# ISOSPI.net
KiCad netlist of a schematic drawn in Altium Designer
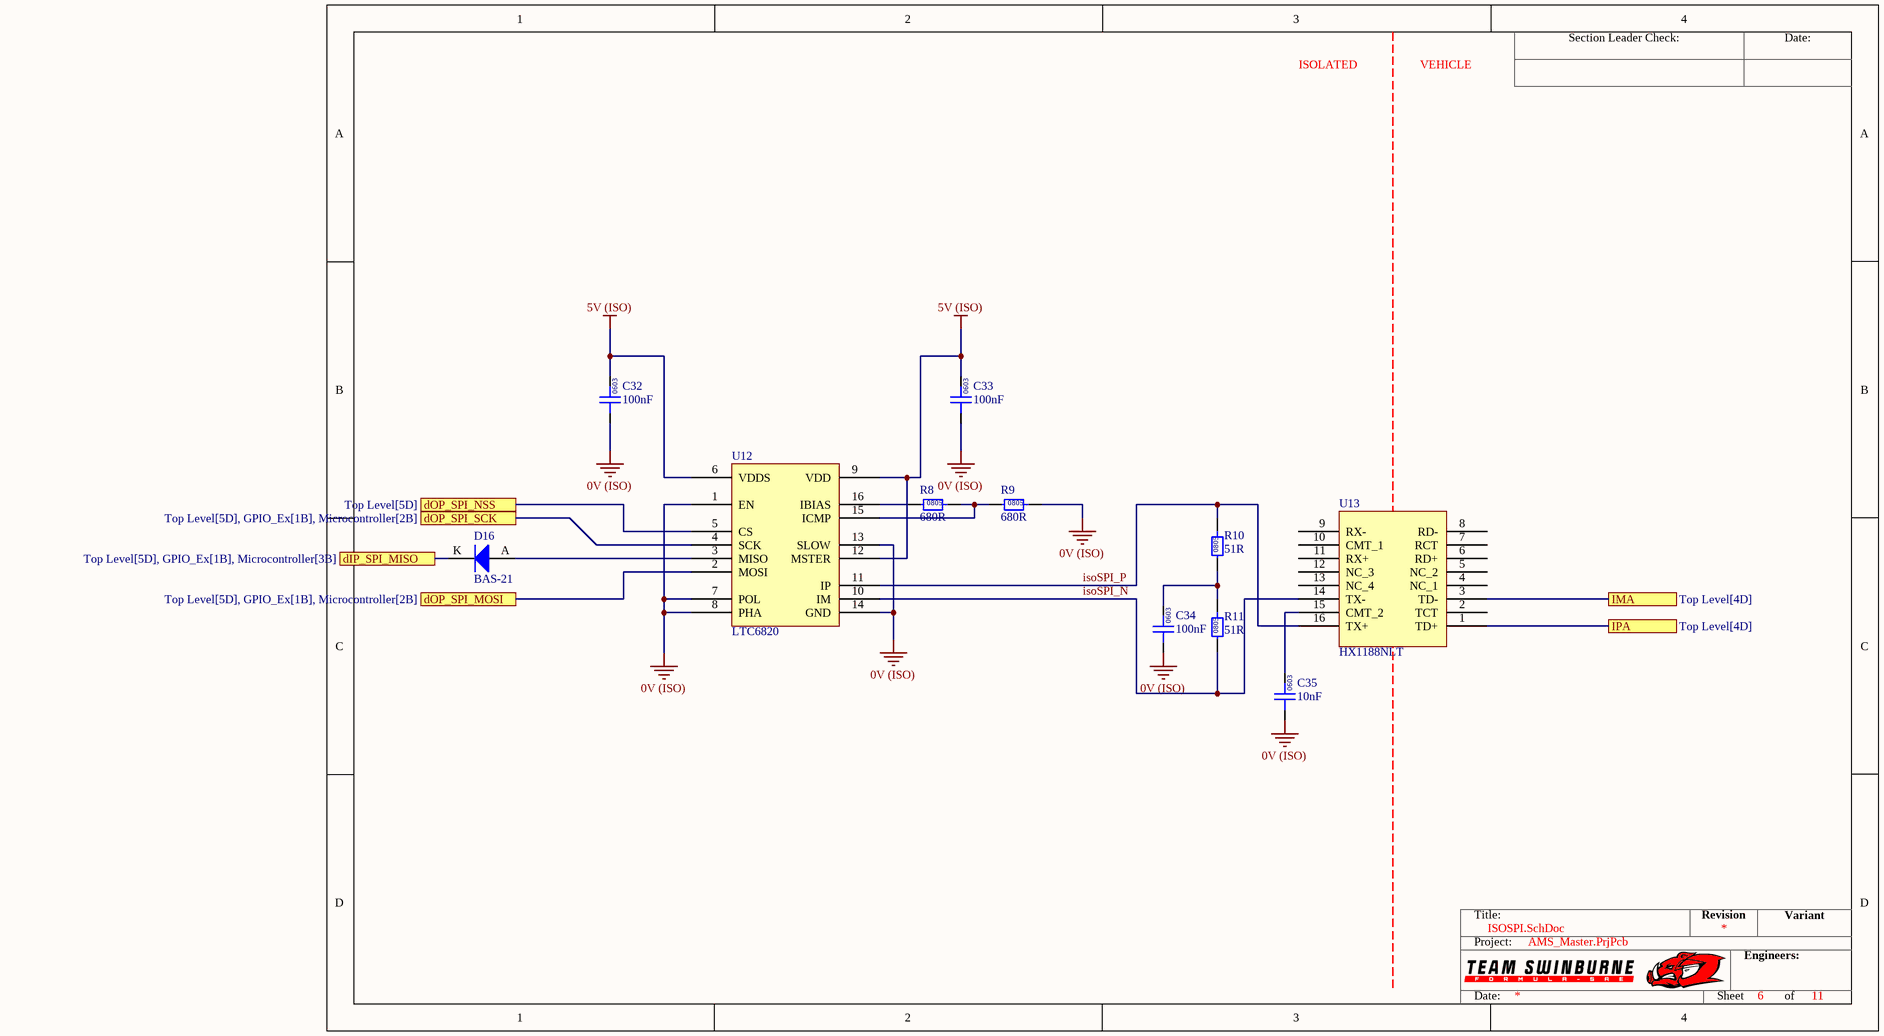
[diagram p0: ISOSPI.SchDoc]

(export (version "E")
  (design (tool "Eeschema 10.0.6"))
  (components
    (comp (ref "C32")
      (value "100nF")
      (footprint "0603")
      (fields
        (field (name "PART NUMBER") "GCM188L81H104KA57D")
        (field (name "MANUFACTURER") "muRata")
        (field (name "TOLERANCE") "±10%")
      )
      (libsource (lib "ts_standard_library") (part "Capacitor 0603"))
    )
    (comp (ref "C33")
      (value "100nF")
      (footprint "0603")
      (fields
        (field (name "PART NUMBER") "GCM188L81H104KA57D")
        (field (name "MANUFACTURER") "muRata")
        (field (name "TOLERANCE") "±10%")
      )
      (libsource (lib "ts_standard_library") (part "Capacitor 0603"))
    )
    (comp (ref "C34")
      (value "100nF")
      (footprint "0603")
      (fields
        (field (name "PART NUMBER") "GCM188L81H104KA57D")
        (field (name "MANUFACTURER") "muRata")
        (field (name "TOLERANCE") "±10%")
      )
      (libsource (lib "ts_standard_library") (part "Capacitor 0603"))
    )
    (comp (ref "C35")
      (value "10nF")
      (footprint "0603")
      (fields
        (field (name "PART NUMBER") "GCM188L81H103KA03D")
        (field (name "MANUFACTURER") "muRata")
        (field (name "TOLERANCE") "±10%")
      )
      (libsource (lib "ts_standard_library") (part "Capacitor 0603"))
    )
    (comp (ref "D16")
      (value "BAS-21")
      (footprint "NEXPERIA_SOT23")
      (fields (field (name "MANUFACTURER") "Nexperia USA Inc."))
      (libsource (lib "ts_standard_library") (part "Diode"))
    )
    (comp (ref "R8")
      (value "680R")
      (footprint "0805")
      (fields
        (field (name "PART NUMBER") "RC0805FR07680RL")
        (field (name "MANUFACTURER") "YAGEO")
        (field (name "TOLERANCE") "0.01")
      )
      (libsource (lib "ts_standard_library") (part "Resistor 0805"))
    )
    (comp (ref "R9")
      (value "680R")
      (footprint "0805")
      (fields
        (field (name "PART NUMBER") "RC0805FR07680RL")
        (field (name "MANUFACTURER") "YAGEO")
        (field (name "TOLERANCE") "0.01")
      )
      (libsource (lib "ts_standard_library") (part "Resistor 0805"))
    )
    (comp (ref "R10")
      (value "51R")
      (footprint "0805")
      (fields
        (field (name "PART NUMBER") "RC0805FR0751RL")
        (field (name "MANUFACTURER") "YAGEO")
        (field (name "TOLERANCE") "0.01")
      )
      (libsource (lib "ts_standard_library") (part "Resistor 0805"))
    )
    (comp (ref "R11")
      (value "51R")
      (footprint "0805")
      (fields
        (field (name "PART NUMBER") "RC0805FR0751RL")
        (field (name "MANUFACTURER") "YAGEO")
        (field (name "TOLERANCE") "0.01")
      )
      (libsource (lib "ts_standard_library") (part "Resistor 0805"))
    )
    (comp (ref "U12")
      (value "LTC6820")
      (footprint "WFQN-16")
      (description "isoSPI Transceiver")
      (fields (field (name "MANUFACTURER") "Analogue Devices"))
      (libsource (lib "ts_standard_library") (part "LTC6820"))
    )
    (comp (ref "U13")
      (value "HX1188NLT")
      (footprint "HX1188NL")
      (description "MODULE XFRMR SGL ETHR LAN 16SOIC")
      (fields (field (name "PART NUMBER") "HX1188NL") (field (name "MANUFACTURER") "Analogue Devices"))
      (libsource (lib "ts_standard_library") (part "HX1188NLT"))
    )
  )
  (nets
    (net (code "1") (name "/IMA") (class "Default")
      (node (ref "U13") (pin "3") (pinfunction "TD-_3") (pintype "passive"))
    )
    (net (code "2") (name "/IPA") (class "Default")
      (node (ref "U13") (pin "1") (pinfunction "TD+_1") (pintype "passive"))
    )
    (net (code "3") (name "/dIP_SPI_MISO") (class "Default")
      (node (ref "D16") (pin "K") (pinfunction "K_K") (pintype "passive"))
    )
    (net (code "4") (name "/dOP_SPI_MOSI") (class "Default")
      (node (ref "U12") (pin "2") (pinfunction "MOSI_2") (pintype "passive"))
    )
    (net (code "5") (name "/dOP_SPI_NSS") (class "Default")
      (node (ref "U12") (pin "5") (pinfunction "CS_5") (pintype "passive"))
    )
    (net (code "6") (name "/dOP_SPI_SCK") (class "Default")
      (node (ref "U12") (pin "4") (pinfunction "SCK_4") (pintype "passive"))
    )
    (net (code "7") (name "/isoSPI_N") (class "Default")
      (node (ref "R11") (pin "1") (pinfunction "1_1") (pintype "passive"))
      (node (ref "U12") (pin "10") (pinfunction "IM_10") (pintype "passive"))
      (node (ref "U13") (pin "14") (pinfunction "TX-_14") (pintype "passive"))
    )
    (net (code "8") (name "/isoSPI_P") (class "Default")
      (node (ref "R10") (pin "2") (pinfunction "2_2") (pintype "passive"))
      (node (ref "U12") (pin "11") (pinfunction "IP_11") (pintype "passive"))
      (node (ref "U13") (pin "16") (pinfunction "TX+_16") (pintype "passive"))
    )
    (net (code "9") (name "0V (ISO)") (class "Default")
      (node (ref "C32") (pin "1") (pinfunction "1_1") (pintype "passive"))
      (node (ref "C33") (pin "1") (pinfunction "1_1") (pintype "passive"))
      (node (ref "C34") (pin "1") (pinfunction "1_1") (pintype "passive"))
      (node (ref "C35") (pin "1") (pinfunction "1_1") (pintype "passive"))
      (node (ref "R9") (pin "2") (pinfunction "2_2") (pintype "passive"))
      (node (ref "U12") (pin "1") (pinfunction "EN_1") (pintype "passive"))
      (node (ref "U12") (pin "13") (pinfunction "SLOW_13") (pintype "passive"))
      (node (ref "U12") (pin "14") (pinfunction "GND_14") (pintype "passive"))
      (node (ref "U12") (pin "7") (pinfunction "POL_7") (pintype "passive"))
      (node (ref "U12") (pin "8") (pinfunction "PHA_8") (pintype "passive"))
    )
    (net (code "10") (name "5V (ISO)") (class "Default")
      (node (ref "C32") (pin "2") (pinfunction "2_2") (pintype "passive"))
      (node (ref "C33") (pin "2") (pinfunction "2_2") (pintype "passive"))
      (node (ref "U12") (pin "12") (pinfunction "MSTER_12") (pintype "passive"))
      (node (ref "U12") (pin "6") (pinfunction "VDDS_6") (pintype "passive"))
      (node (ref "U12") (pin "9") (pinfunction "VDD_9") (pintype "passive"))
    )
    (net (code "11") (name "Net-(C34-Pad2)") (class "Default")
      (node (ref "C34") (pin "2") (pinfunction "2_2") (pintype "passive"))
      (node (ref "R10") (pin "1") (pinfunction "1_1") (pintype "passive"))
      (node (ref "R11") (pin "2") (pinfunction "2_2") (pintype "passive"))
    )
    (net (code "12") (name "Net-(U12-IBIAS)") (class "Default")
      (node (ref "R8") (pin "1") (pinfunction "1_1") (pintype "passive"))
      (node (ref "U12") (pin "16") (pinfunction "IBIAS_16") (pintype "passive"))
    )
    (net (code "13") (name "Net-(U12-ICMP)") (class "Default")
      (node (ref "R8") (pin "2") (pinfunction "2_2") (pintype "passive"))
      (node (ref "R9") (pin "1") (pinfunction "1_1") (pintype "passive"))
      (node (ref "U12") (pin "15") (pinfunction "ICMP_15") (pintype "passive"))
    )
    (net (code "14") (name "Net-(U12-MISO)") (class "Default")
      (node (ref "D16") (pin "A") (pinfunction "A_A") (pintype "passive"))
      (node (ref "U12") (pin "3") (pinfunction "MISO_3") (pintype "passive"))
    )
    (net (code "15") (name "Net-(U13-CMT_2)") (class "Default")
      (node (ref "C35") (pin "2") (pinfunction "2_2") (pintype "passive"))
      (node (ref "U13") (pin "15") (pinfunction "CMT_2_15") (pintype "passive"))
    )
    (net (code "16") (name "unconnected-(U13-CMT_1-Pad10)") (class "Default")
      (node (ref "U13") (pin "10") (pinfunction "CMT_1_10") (pintype "passive"))
    )
    (net (code "17") (name "unconnected-(U13-NC_1-Pad4)") (class "Default")
      (node (ref "U13") (pin "4") (pinfunction "NC_1_4") (pintype "passive"))
    )
    (net (code "18") (name "unconnected-(U13-NC_2-Pad5)") (class "Default")
      (node (ref "U13") (pin "5") (pinfunction "NC_2_5") (pintype "passive"))
    )
    (net (code "19") (name "unconnected-(U13-NC_3-Pad12)") (class "Default")
      (node (ref "U13") (pin "12") (pinfunction "NC_3_12") (pintype "passive"))
    )
    (net (code "20") (name "unconnected-(U13-NC_4-Pad13)") (class "Default")
      (node (ref "U13") (pin "13") (pinfunction "NC_4_13") (pintype "passive"))
    )
    (net (code "21") (name "unconnected-(U13-RCT-Pad7)") (class "Default")
      (node (ref "U13") (pin "7") (pinfunction "RCT_7") (pintype "passive"))
    )
    (net (code "22") (name "unconnected-(U13-RD+-Pad6)") (class "Default")
      (node (ref "U13") (pin "6") (pinfunction "RD+_6") (pintype "passive"))
    )
    (net (code "23") (name "unconnected-(U13-RD--Pad8)") (class "Default")
      (node (ref "U13") (pin "8") (pinfunction "RD-_8") (pintype "passive"))
    )
    (net (code "24") (name "unconnected-(U13-RX+-Pad11)") (class "Default")
      (node (ref "U13") (pin "11") (pinfunction "RX+_11") (pintype "passive"))
    )
    (net (code "25") (name "unconnected-(U13-RX--Pad9)") (class "Default")
      (node (ref "U13") (pin "9") (pinfunction "RX-_9") (pintype "passive"))
    )
    (net (code "26") (name "unconnected-(U13-TCT-Pad2)") (class "Default")
      (node (ref "U13") (pin "2") (pinfunction "TCT_2") (pintype "passive"))
    )
  )
)
